# omenpia.net
KiCad netlist of a schematic drawn in EAGLE
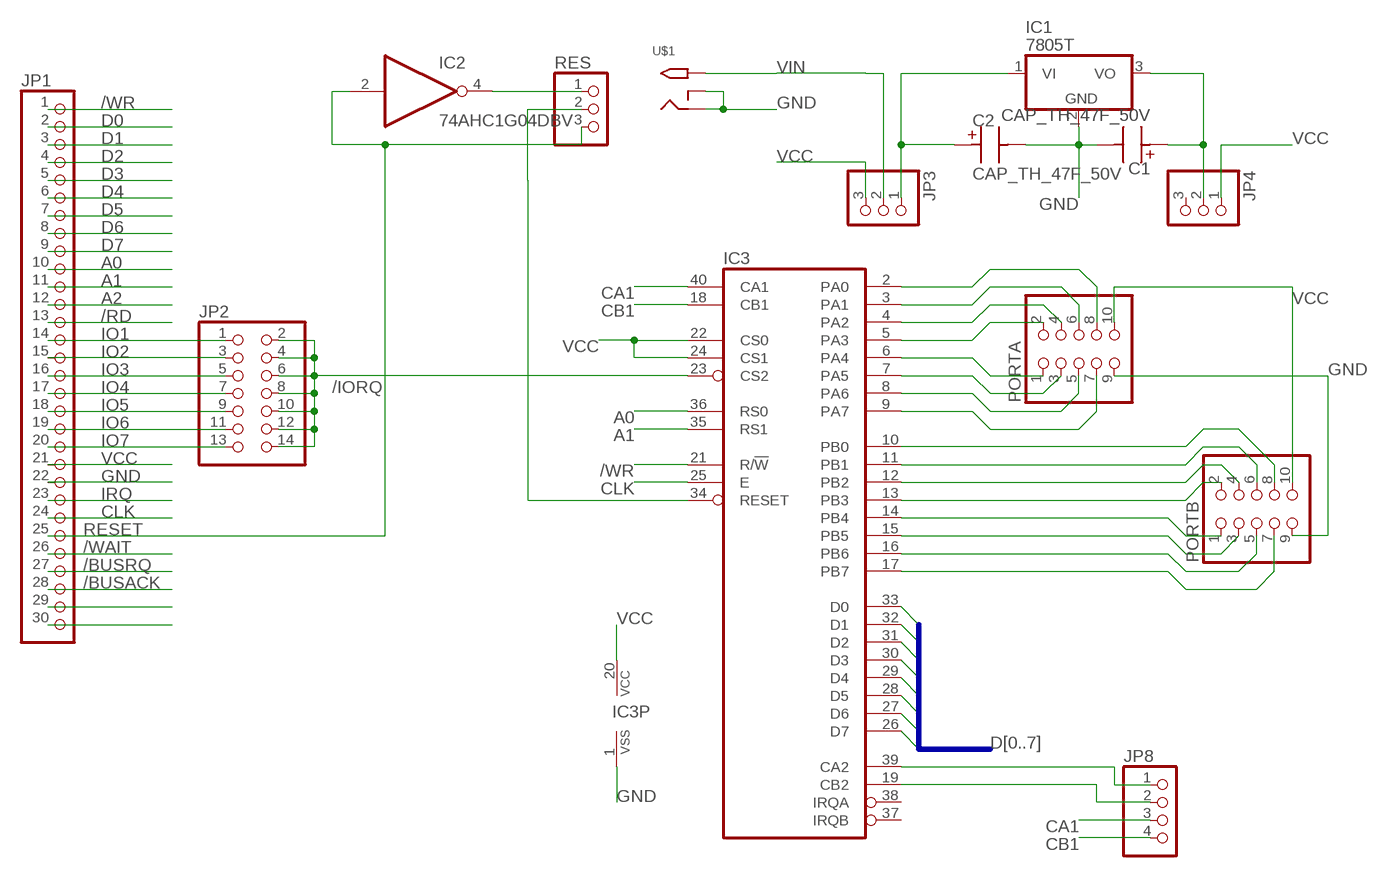
[diagram p0: schematic, sheet 1]

(export (version "E")
  (design (tool "Eeschema 10.0.6"))
  (components
    (comp (ref "C1")
      (value "CAP_TH_47F_50V")
      (footprint "eagle-import:CAP_TH_P25_D63_POL")
      (libsource (lib "eagle-import") (part "CAP_TH_47F_50V"))
    )
    (comp (ref "C2")
      (value "CAP_TH_47F_50V")
      (footprint "eagle-import:CAP_TH_P25_D63_POL")
      (libsource (lib "eagle-import") (part "CAP_TH_47F_50V"))
    )
    (comp (ref "IC1")
      (value "7805T")
      (footprint "eagle-import:TO220H")
      (libsource (lib "eagle-import") (part "78T05"))
    )
    (comp (ref "IC2")
      (value "74AHC1G04DBV")
      (footprint "eagle-import:SOT23-5")
      (libsource (lib "eagle-import") (part "741G04DBVAHC"))
    )
    (comp (ref "IC3")
      (value "6821")
      (footprint "eagle-import:DIL40")
      (fields (field (name "MF") "NTE ELECTRONICS") (field (name "MPN") "NTE6821"))
      (libsource (lib "eagle-import") (part "6821"))
    )
    (comp (ref "JP1")
      (value "PINHD-1X30")
      (footprint "eagle-import:1X30")
      (libsource (lib "eagle-import") (part "PINHD-1X30"))
    )
    (comp (ref "JP2")
      (value "PINHD-2X7")
      (footprint "eagle-import:2X07")
      (libsource (lib "eagle-import") (part "PINHD-2X7"))
    )
    (comp (ref "JP3")
      (value "PINHD-1X3")
      (footprint "eagle-import:1X03")
      (libsource (lib "eagle-import") (part "PINHD-1X3"))
    )
    (comp (ref "JP4")
      (value "PINHD-1X3")
      (footprint "eagle-import:1X03")
      (libsource (lib "eagle-import") (part "PINHD-1X3"))
    )
    (comp (ref "JP8")
      (value "PINHD-1X4")
      (footprint "eagle-import:1X04")
      (libsource (lib "eagle-import") (part "PINHD-1X4"))
    )
    (comp (ref "PORTA")
      (value "PINHD-2X5")
      (footprint "eagle-import:2X05")
      (libsource (lib "eagle-import") (part "PINHD-2X5"))
    )
    (comp (ref "PORTB")
      (value "PINHD-2X5")
      (footprint "eagle-import:2X05")
      (libsource (lib "eagle-import") (part "PINHD-2X5"))
    )
    (comp (ref "RES")
      (value "PINHD-1X3")
      (footprint "eagle-import:1X03")
      (libsource (lib "eagle-import") (part "PINHD-1X3"))
    )
    (comp (ref "U$1")
      (value "2.1MMJACKTHM")
      (footprint "eagle-import:PJ-102A")
      (libsource (lib "eagle-import") (part "2.1MMJACKTHM"))
    )
  )
  (nets
    (net (code "1") (name "/A0") (class "Default")
      (node (ref "IC3") (pin "36") (pinfunction "RS0_36") (pintype "input"))
      (node (ref "JP1") (pin "10") (pinfunction "10_10") (pintype "passive"))
    )
    (net (code "2") (name "/A1") (class "Default")
      (node (ref "IC3") (pin "35") (pinfunction "RS1_35") (pintype "input"))
      (node (ref "JP1") (pin "11") (pinfunction "11_11") (pintype "passive"))
    )
    (net (code "3") (name "/A2") (class "Default")
      (node (ref "JP1") (pin "12") (pinfunction "12_12") (pintype "passive"))
    )
    (net (code "4") (name "/CA1") (class "Default")
      (node (ref "IC3") (pin "40") (pinfunction "CA1_40") (pintype "input"))
      (node (ref "JP8") (pin "3") (pinfunction "3_3") (pintype "passive"))
    )
    (net (code "5") (name "/CB1") (class "Default")
      (node (ref "IC3") (pin "18") (pinfunction "CB1_18") (pintype "input"))
      (node (ref "JP8") (pin "4") (pinfunction "4_4") (pintype "passive"))
    )
    (net (code "6") (name "/CLK") (class "Default")
      (node (ref "IC3") (pin "25") (pinfunction "E_25") (pintype "input"))
      (node (ref "JP1") (pin "24") (pinfunction "24_24") (pintype "passive"))
    )
    (net (code "7") (name "/D0") (class "Default")
      (node (ref "IC3") (pin "33") (pinfunction "D0_33") (pintype "bidirectional"))
      (node (ref "JP1") (pin "2") (pinfunction "2_2") (pintype "passive"))
    )
    (net (code "8") (name "/D1") (class "Default")
      (node (ref "IC3") (pin "32") (pinfunction "D1_32") (pintype "bidirectional"))
      (node (ref "JP1") (pin "3") (pinfunction "3_3") (pintype "passive"))
    )
    (net (code "9") (name "/D2") (class "Default")
      (node (ref "IC3") (pin "31") (pinfunction "D2_31") (pintype "bidirectional"))
      (node (ref "JP1") (pin "4") (pinfunction "4_4") (pintype "passive"))
    )
    (net (code "10") (name "/D3") (class "Default")
      (node (ref "IC3") (pin "30") (pinfunction "D3_30") (pintype "bidirectional"))
      (node (ref "JP1") (pin "5") (pinfunction "5_5") (pintype "passive"))
    )
    (net (code "11") (name "/D4") (class "Default")
      (node (ref "IC3") (pin "29") (pinfunction "D4_29") (pintype "bidirectional"))
      (node (ref "JP1") (pin "6") (pinfunction "6_6") (pintype "passive"))
    )
    (net (code "12") (name "/D5") (class "Default")
      (node (ref "IC3") (pin "28") (pinfunction "D5_28") (pintype "bidirectional"))
      (node (ref "JP1") (pin "7") (pinfunction "7_7") (pintype "passive"))
    )
    (net (code "13") (name "/D6") (class "Default")
      (node (ref "IC3") (pin "27") (pinfunction "D6_27") (pintype "bidirectional"))
      (node (ref "JP1") (pin "8") (pinfunction "8_8") (pintype "passive"))
    )
    (net (code "14") (name "/D7") (class "Default")
      (node (ref "IC3") (pin "26") (pinfunction "D7_26") (pintype "bidirectional"))
      (node (ref "JP1") (pin "9") (pinfunction "9_9") (pintype "passive"))
    )
    (net (code "16") (name "/GND") (class "Default")
      (node (ref "C1") (pin "P$M") (pinfunction "P$M_P$M") (pintype "passive"))
      (node (ref "C2") (pin "P$M") (pinfunction "P$M_P$M") (pintype "passive"))
      (node (ref "IC1") (pin "2") (pinfunction "GND_2") (pintype "passive"))
      (node (ref "IC3") (pin "1") (pinfunction "VSS_1") (pintype "power_in"))
      (node (ref "JP1") (pin "22") (pinfunction "22_22") (pintype "passive"))
      (node (ref "PORTA") (pin "9") (pinfunction "9_9") (pintype "passive"))
      (node (ref "PORTB") (pin "9") (pinfunction "9_9") (pintype "passive"))
      (node (ref "U$1") (pin "RING") (pinfunction "RING_RING") (pintype "bidirectional"))
      (node (ref "U$1") (pin "RING_SW") (pinfunction "RING_SW_RING_SW") (pintype "bidirectional"))
    )
    (net (code "17") (name "/IO1") (class "Default")
      (node (ref "JP1") (pin "14") (pinfunction "14_14") (pintype "passive"))
      (node (ref "JP2") (pin "1") (pinfunction "1_1") (pintype "passive"))
    )
    (net (code "18") (name "/IO2") (class "Default")
      (node (ref "JP1") (pin "15") (pinfunction "15_15") (pintype "passive"))
      (node (ref "JP2") (pin "3") (pinfunction "3_3") (pintype "passive"))
    )
    (net (code "19") (name "/IO3") (class "Default")
      (node (ref "JP1") (pin "16") (pinfunction "16_16") (pintype "passive"))
      (node (ref "JP2") (pin "5") (pinfunction "5_5") (pintype "passive"))
    )
    (net (code "20") (name "/IO4") (class "Default")
      (node (ref "JP1") (pin "17") (pinfunction "17_17") (pintype "passive"))
      (node (ref "JP2") (pin "7") (pinfunction "7_7") (pintype "passive"))
    )
    (net (code "21") (name "/IO5") (class "Default")
      (node (ref "JP1") (pin "18") (pinfunction "18_18") (pintype "passive"))
      (node (ref "JP2") (pin "9") (pinfunction "9_9") (pintype "passive"))
    )
    (net (code "22") (name "/IO6") (class "Default")
      (node (ref "JP1") (pin "19") (pinfunction "19_19") (pintype "passive"))
      (node (ref "JP2") (pin "11") (pinfunction "11_11") (pintype "passive"))
    )
    (net (code "23") (name "/IO7") (class "Default")
      (node (ref "JP1") (pin "20") (pinfunction "20_20") (pintype "passive"))
      (node (ref "JP2") (pin "13") (pinfunction "13_13") (pintype "passive"))
    )
    (net (code "24") (name "/IRQ") (class "Default")
      (node (ref "JP1") (pin "23") (pinfunction "23_23") (pintype "passive"))
    )
    (net (code "25") (name "/RESET") (class "Default")
      (node (ref "IC2") (pin "2") (pinfunction "I_2") (pintype "input"))
      (node (ref "JP1") (pin "25") (pinfunction "25_25") (pintype "passive"))
      (node (ref "RES") (pin "3") (pinfunction "3_3") (pintype "passive"))
    )
    (net (code "26") (name "/VCC") (class "Default")
      (node (ref "IC3") (pin "20") (pinfunction "VCC_20") (pintype "power_in"))
      (node (ref "IC3") (pin "22") (pinfunction "CS0_22") (pintype "input"))
      (node (ref "IC3") (pin "24") (pinfunction "CS1_24") (pintype "input"))
      (node (ref "JP1") (pin "21") (pinfunction "21_21") (pintype "passive"))
      (node (ref "JP3") (pin "3") (pinfunction "3_3") (pintype "passive"))
      (node (ref "JP4") (pin "1") (pinfunction "1_1") (pintype "passive"))
      (node (ref "PORTA") (pin "10") (pinfunction "10_10") (pintype "passive"))
      (node (ref "PORTB") (pin "10") (pinfunction "10_10") (pintype "passive"))
    )
    (net (code "27") (name "/VIN") (class "Default")
      (node (ref "JP3") (pin "2") (pinfunction "2_2") (pintype "passive"))
      (node (ref "U$1") (pin "TIP") (pinfunction "TIP_TIP") (pintype "bidirectional"))
    )
    (net (code "28") (name "/{slash}BUSACK") (class "Default")
      (node (ref "JP1") (pin "28") (pinfunction "28_28") (pintype "passive"))
    )
    (net (code "29") (name "/{slash}BUSRQ") (class "Default")
      (node (ref "JP1") (pin "27") (pinfunction "27_27") (pintype "passive"))
    )
    (net (code "30") (name "/{slash}IORQ") (class "Default")
      (node (ref "IC3") (pin "23") (pinfunction "CS2_23") (pintype "input"))
      (node (ref "JP2") (pin "10") (pinfunction "10_10") (pintype "passive"))
      (node (ref "JP2") (pin "12") (pinfunction "12_12") (pintype "passive"))
      (node (ref "JP2") (pin "14") (pinfunction "14_14") (pintype "passive"))
      (node (ref "JP2") (pin "2") (pinfunction "2_2") (pintype "passive"))
      (node (ref "JP2") (pin "4") (pinfunction "4_4") (pintype "passive"))
      (node (ref "JP2") (pin "6") (pinfunction "6_6") (pintype "passive"))
      (node (ref "JP2") (pin "8") (pinfunction "8_8") (pintype "passive"))
    )
    (net (code "31") (name "/{slash}RD") (class "Default")
      (node (ref "JP1") (pin "13") (pinfunction "13_13") (pintype "passive"))
    )
    (net (code "32") (name "/{slash}WAIT") (class "Default")
      (node (ref "JP1") (pin "26") (pinfunction "26_26") (pintype "passive"))
    )
    (net (code "33") (name "/{slash}WR") (class "Default")
      (node (ref "IC3") (pin "21") (pinfunction "R/~{W}_21") (pintype "input"))
      (node (ref "JP1") (pin "1") (pinfunction "1_1") (pintype "passive"))
    )
    (net (code "34") (name "Net-(IC1-VI)") (class "Default")
      (node (ref "C2") (pin "P$P") (pinfunction "P$P_P$P") (pintype "passive"))
      (node (ref "IC1") (pin "1") (pinfunction "VI_1") (pintype "input"))
      (node (ref "JP3") (pin "1") (pinfunction "1_1") (pintype "passive"))
    )
    (net (code "35") (name "Net-(IC1-VO)") (class "Default")
      (node (ref "C1") (pin "P$P") (pinfunction "P$P_P$P") (pintype "passive"))
      (node (ref "IC1") (pin "3") (pinfunction "VO_3") (pintype "passive"))
      (node (ref "JP4") (pin "2") (pinfunction "2_2") (pintype "passive"))
    )
    (net (code "36") (name "Net-(IC2A-O)") (class "Default")
      (node (ref "IC2") (pin "4") (pinfunction "O_4") (pintype "output"))
      (node (ref "RES") (pin "1") (pinfunction "1_1") (pintype "passive"))
    )
    (net (code "37") (name "Net-(IC3A-CA2)") (class "Default")
      (node (ref "IC3") (pin "39") (pinfunction "CA2_39") (pintype "bidirectional"))
      (node (ref "JP8") (pin "1") (pinfunction "1_1") (pintype "passive"))
    )
    (net (code "38") (name "Net-(IC3A-CB2)") (class "Default")
      (node (ref "IC3") (pin "19") (pinfunction "CB2_19") (pintype "bidirectional"))
      (node (ref "JP8") (pin "2") (pinfunction "2_2") (pintype "passive"))
    )
    (net (code "39") (name "Net-(IC3A-PA0)") (class "Default")
      (node (ref "IC3") (pin "2") (pinfunction "PA0_2") (pintype "bidirectional"))
      (node (ref "PORTA") (pin "8") (pinfunction "8_8") (pintype "passive"))
    )
    (net (code "40") (name "Net-(IC3A-PA1)") (class "Default")
      (node (ref "IC3") (pin "3") (pinfunction "PA1_3") (pintype "bidirectional"))
      (node (ref "PORTA") (pin "6") (pinfunction "6_6") (pintype "passive"))
    )
    (net (code "41") (name "Net-(IC3A-PA2)") (class "Default")
      (node (ref "IC3") (pin "4") (pinfunction "PA2_4") (pintype "bidirectional"))
      (node (ref "PORTA") (pin "4") (pinfunction "4_4") (pintype "passive"))
    )
    (net (code "42") (name "Net-(IC3A-PA3)") (class "Default")
      (node (ref "IC3") (pin "5") (pinfunction "PA3_5") (pintype "bidirectional"))
      (node (ref "PORTA") (pin "2") (pinfunction "2_2") (pintype "passive"))
    )
    (net (code "43") (name "Net-(IC3A-PA4)") (class "Default")
      (node (ref "IC3") (pin "6") (pinfunction "PA4_6") (pintype "bidirectional"))
      (node (ref "PORTA") (pin "1") (pinfunction "1_1") (pintype "passive"))
    )
    (net (code "44") (name "Net-(IC3A-PA5)") (class "Default")
      (node (ref "IC3") (pin "7") (pinfunction "PA5_7") (pintype "bidirectional"))
      (node (ref "PORTA") (pin "3") (pinfunction "3_3") (pintype "passive"))
    )
    (net (code "45") (name "Net-(IC3A-PA6)") (class "Default")
      (node (ref "IC3") (pin "8") (pinfunction "PA6_8") (pintype "bidirectional"))
      (node (ref "PORTA") (pin "5") (pinfunction "5_5") (pintype "passive"))
    )
    (net (code "46") (name "Net-(IC3A-PA7)") (class "Default")
      (node (ref "IC3") (pin "9") (pinfunction "PA7_9") (pintype "bidirectional"))
      (node (ref "PORTA") (pin "7") (pinfunction "7_7") (pintype "passive"))
    )
    (net (code "47") (name "Net-(IC3A-PB0)") (class "Default")
      (node (ref "IC3") (pin "10") (pinfunction "PB0_10") (pintype "bidirectional"))
      (node (ref "PORTB") (pin "8") (pinfunction "8_8") (pintype "passive"))
    )
    (net (code "48") (name "Net-(IC3A-PB1)") (class "Default")
      (node (ref "IC3") (pin "11") (pinfunction "PB1_11") (pintype "bidirectional"))
      (node (ref "PORTB") (pin "6") (pinfunction "6_6") (pintype "passive"))
    )
    (net (code "49") (name "Net-(IC3A-PB2)") (class "Default")
      (node (ref "IC3") (pin "12") (pinfunction "PB2_12") (pintype "bidirectional"))
      (node (ref "PORTB") (pin "4") (pinfunction "4_4") (pintype "passive"))
    )
    (net (code "50") (name "Net-(IC3A-PB3)") (class "Default")
      (node (ref "IC3") (pin "13") (pinfunction "PB3_13") (pintype "bidirectional"))
      (node (ref "PORTB") (pin "2") (pinfunction "2_2") (pintype "passive"))
    )
    (net (code "51") (name "Net-(IC3A-PB4)") (class "Default")
      (node (ref "IC3") (pin "14") (pinfunction "PB4_14") (pintype "bidirectional"))
      (node (ref "PORTB") (pin "1") (pinfunction "1_1") (pintype "passive"))
    )
    (net (code "52") (name "Net-(IC3A-PB5)") (class "Default")
      (node (ref "IC3") (pin "15") (pinfunction "PB5_15") (pintype "bidirectional"))
      (node (ref "PORTB") (pin "3") (pinfunction "3_3") (pintype "passive"))
    )
    (net (code "53") (name "Net-(IC3A-PB6)") (class "Default")
      (node (ref "IC3") (pin "16") (pinfunction "PB6_16") (pintype "bidirectional"))
      (node (ref "PORTB") (pin "5") (pinfunction "5_5") (pintype "passive"))
    )
    (net (code "54") (name "Net-(IC3A-PB7)") (class "Default")
      (node (ref "IC3") (pin "17") (pinfunction "PB7_17") (pintype "bidirectional"))
      (node (ref "PORTB") (pin "7") (pinfunction "7_7") (pintype "passive"))
    )
    (net (code "55") (name "Net-(IC3A-RESET)") (class "Default")
      (node (ref "IC3") (pin "34") (pinfunction "RESET_34") (pintype "input"))
      (node (ref "RES") (pin "2") (pinfunction "2_2") (pintype "passive"))
    )
    (net (code "56") (name "unconnected-(IC3A-IRQA-Pad38)") (class "Default")
      (node (ref "IC3") (pin "38") (pinfunction "IRQA_38") (pintype "open_collector"))
    )
    (net (code "57") (name "unconnected-(IC3A-IRQB-Pad37)") (class "Default")
      (node (ref "IC3") (pin "37") (pinfunction "IRQB_37") (pintype "open_collector"))
    )
    (net (code "58") (name "unconnected-(JP1-Pad29)") (class "Default")
      (node (ref "JP1") (pin "29") (pinfunction "29_29") (pintype "passive"))
    )
    (net (code "59") (name "unconnected-(JP1-Pad30)") (class "Default")
      (node (ref "JP1") (pin "30") (pinfunction "30_30") (pintype "passive"))
    )
    (net (code "60") (name "unconnected-(JP4-Pad3)") (class "Default")
      (node (ref "JP4") (pin "3") (pinfunction "3_3") (pintype "passive"))
    )
  )
)
